# display.net
KiCad netlist of a schematic drawn in Altium Designer
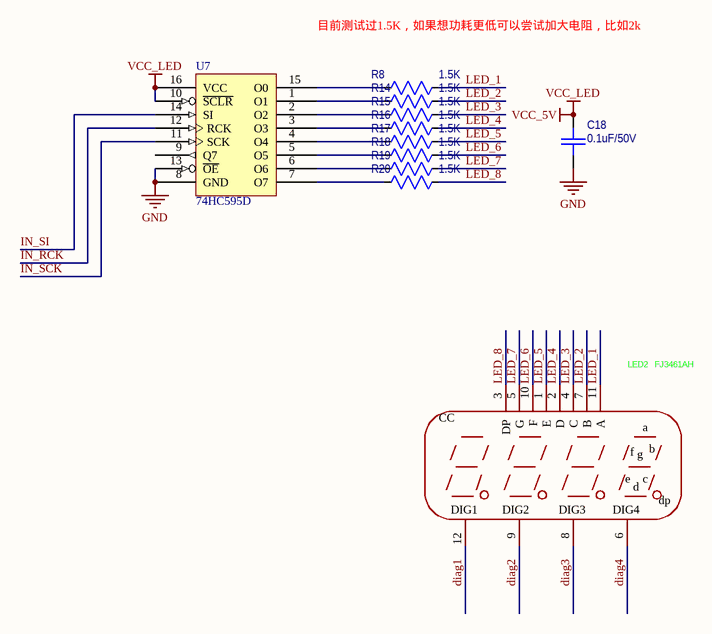
[diagram p0: display.SchDoc]

(export (version "E")
  (design (tool "Eeschema 10.0.6"))
  (components
    (comp (ref "C18")
      (value "0.1uF/50V")
      (footprint "CAPC1608X092N_0603")
      (description "Capacitor, MLCC")
      (fields (field (name "MANUFACTURER") "KEMET") (field (name "PARTNUMBER") "C0603C104M5RACTU"))
      (libsource (lib "Karl") (part "Capacitor_0603"))
    )
    (comp (ref "LED2")
      (value "FJ3461AH")
      (footprint "LED-SEG-TH_12P-L30.0-W14.0-P2.54-S10.26-BL:LED-SEG-TH_12P-L30.0-W14.0-P2.54-S10.26-BL")
      (fields (field (name "MANUFACTURER") "志浩") (field (name "MANUFACTURER PART") "FJ5461AH 红色"))
      (libsource (lib "altium-import") (part "root_0_FJ5461AH 红色_"))
    )
    (comp (ref "R8")
      (value "1.5K")
      (footprint "RESC1608X055N_0603")
      (description "Resistor, Standard")
      (fields (field (name "MANUFACTURER") "Yageo") (field (name "PARTNUMBER") "RC0603FR-1075KL"))
      (libsource (lib "Karl") (part "Resistor_0603"))
    )
    (comp (ref "R14")
      (value "1.5K")
      (footprint "RESC1608X055N_0603")
      (description "Resistor, Standard")
      (fields (field (name "MANUFACTURER") "Yageo") (field (name "PARTNUMBER") "RC0603FR-1075KL"))
      (libsource (lib "Karl") (part "Resistor_0603"))
    )
    (comp (ref "R15")
      (value "1.5K")
      (footprint "RESC1608X055N_0603")
      (description "Resistor, Standard")
      (fields (field (name "MANUFACTURER") "Yageo") (field (name "PARTNUMBER") "RC0603FR-1075KL"))
      (libsource (lib "Karl") (part "Resistor_0603"))
    )
    (comp (ref "R16")
      (value "1.5K")
      (footprint "RESC1608X055N_0603")
      (description "Resistor, Standard")
      (fields (field (name "MANUFACTURER") "Yageo") (field (name "PARTNUMBER") "RC0603FR-1075KL"))
      (libsource (lib "Karl") (part "Resistor_0603"))
    )
    (comp (ref "R17")
      (value "1.5K")
      (footprint "RESC1608X055N_0603")
      (description "Resistor, Standard")
      (fields (field (name "MANUFACTURER") "Yageo") (field (name "PARTNUMBER") "RC0603FR-1075KL"))
      (libsource (lib "Karl") (part "Resistor_0603"))
    )
    (comp (ref "R18")
      (value "1.5K")
      (footprint "RESC1608X055N_0603")
      (description "Resistor, Standard")
      (fields (field (name "MANUFACTURER") "Yageo") (field (name "PARTNUMBER") "RC0603FR-1075KL"))
      (libsource (lib "Karl") (part "Resistor_0603"))
    )
    (comp (ref "R19")
      (value "1.5K")
      (footprint "RESC1608X055N_0603")
      (description "Resistor, Standard")
      (fields (field (name "MANUFACTURER") "Yageo") (field (name "PARTNUMBER") "RC0603FR-1075KL"))
      (libsource (lib "Karl") (part "Resistor_0603"))
    )
    (comp (ref "R20")
      (value "1.5K")
      (footprint "RESC1608X055N_0603")
      (description "Resistor, Standard")
      (fields (field (name "MANUFACTURER") "Yageo") (field (name "PARTNUMBER") "RC0603FR-1075KL"))
      (libsource (lib "Karl") (part "Resistor_0603"))
    )
    (comp (ref "U7")
      (value "74HC595D")
      (footprint "SOIC-16_L9.9-W3.9-P1.27-LS6.0-BL:SOIC-16_L9.9-W3.9-P1.27-LS6.0-BL")
      (libsource (lib "DI16") (part "74HC595"))
    )
  )
  (nets
    (net (code "1") (name "/IN_RCK") (class "Default")
      (node (ref "U7") (pin "12") (pinfunction "RCK_12") (pintype "input"))
    )
    (net (code "2") (name "/IN_SCK") (class "Default")
      (node (ref "U7") (pin "11") (pinfunction "SCK_11") (pintype "input"))
    )
    (net (code "3") (name "/IN_SI") (class "Default")
      (node (ref "U7") (pin "14") (pinfunction "SI_14") (pintype "input"))
    )
    (net (code "4") (name "/LED_1") (class "Default")
      (node (ref "LED2") (pin "11") (pinfunction "A_11") (pintype "passive"))
      (node (ref "R8") (pin "1") (pinfunction "1_1") (pintype "passive"))
    )
    (net (code "5") (name "/LED_2") (class "Default")
      (node (ref "LED2") (pin "7") (pinfunction "B_7") (pintype "passive"))
      (node (ref "R14") (pin "1") (pinfunction "1_1") (pintype "passive"))
    )
    (net (code "6") (name "/LED_3") (class "Default")
      (node (ref "LED2") (pin "4") (pinfunction "C_4") (pintype "passive"))
      (node (ref "R15") (pin "1") (pinfunction "1_1") (pintype "passive"))
    )
    (net (code "7") (name "/LED_4") (class "Default")
      (node (ref "LED2") (pin "2") (pinfunction "D_2") (pintype "passive"))
      (node (ref "R16") (pin "1") (pinfunction "1_1") (pintype "passive"))
    )
    (net (code "8") (name "/LED_5") (class "Default")
      (node (ref "LED2") (pin "1") (pinfunction "E_1") (pintype "passive"))
      (node (ref "R17") (pin "1") (pinfunction "1_1") (pintype "passive"))
    )
    (net (code "9") (name "/LED_6") (class "Default")
      (node (ref "LED2") (pin "10") (pinfunction "F_10") (pintype "passive"))
      (node (ref "R18") (pin "1") (pinfunction "1_1") (pintype "passive"))
    )
    (net (code "10") (name "/LED_7") (class "Default")
      (node (ref "LED2") (pin "5") (pinfunction "G_5") (pintype "passive"))
      (node (ref "R19") (pin "1") (pinfunction "1_1") (pintype "passive"))
    )
    (net (code "11") (name "/LED_8") (class "Default")
      (node (ref "LED2") (pin "3") (pinfunction "DP_3") (pintype "passive"))
      (node (ref "R20") (pin "1") (pinfunction "1_1") (pintype "passive"))
    )
    (net (code "12") (name "/diag1") (class "Default")
      (node (ref "LED2") (pin "12") (pinfunction "DIG1_12") (pintype "passive"))
    )
    (net (code "13") (name "/diag2") (class "Default")
      (node (ref "LED2") (pin "9") (pinfunction "DIG2_9") (pintype "passive"))
    )
    (net (code "14") (name "/diag3") (class "Default")
      (node (ref "LED2") (pin "8") (pinfunction "DIG3_8") (pintype "passive"))
    )
    (net (code "15") (name "/diag4") (class "Default")
      (node (ref "LED2") (pin "6") (pinfunction "DIG4_6") (pintype "passive"))
    )
    (net (code "16") (name "GND") (class "Default")
      (node (ref "C18") (pin "2") (pinfunction "2_2") (pintype "passive"))
      (node (ref "U7") (pin "13") (pinfunction "~{OE}_13") (pintype "input"))
      (node (ref "U7") (pin "8") (pinfunction "GND_8") (pintype "power_in"))
    )
    (net (code "17") (name "Net-(U7-O0)") (class "Default")
      (node (ref "R8") (pin "2") (pinfunction "2_2") (pintype "passive"))
      (node (ref "U7") (pin "15") (pinfunction "O0_15") (pintype "tri_state"))
    )
    (net (code "18") (name "Net-(U7-O1)") (class "Default")
      (node (ref "R14") (pin "2") (pinfunction "2_2") (pintype "passive"))
      (node (ref "U7") (pin "1") (pinfunction "O1_1") (pintype "tri_state"))
    )
    (net (code "19") (name "Net-(U7-O2)") (class "Default")
      (node (ref "R15") (pin "2") (pinfunction "2_2") (pintype "passive"))
      (node (ref "U7") (pin "2") (pinfunction "O2_2") (pintype "tri_state"))
    )
    (net (code "20") (name "Net-(U7-O3)") (class "Default")
      (node (ref "R16") (pin "2") (pinfunction "2_2") (pintype "passive"))
      (node (ref "U7") (pin "3") (pinfunction "O3_3") (pintype "tri_state"))
    )
    (net (code "21") (name "Net-(U7-O4)") (class "Default")
      (node (ref "R17") (pin "2") (pinfunction "2_2") (pintype "passive"))
      (node (ref "U7") (pin "4") (pinfunction "O4_4") (pintype "tri_state"))
    )
    (net (code "22") (name "Net-(U7-O5)") (class "Default")
      (node (ref "R18") (pin "2") (pinfunction "2_2") (pintype "passive"))
      (node (ref "U7") (pin "5") (pinfunction "O5_5") (pintype "tri_state"))
    )
    (net (code "23") (name "Net-(U7-O6)") (class "Default")
      (node (ref "R19") (pin "2") (pinfunction "2_2") (pintype "passive"))
      (node (ref "U7") (pin "6") (pinfunction "O6_6") (pintype "tri_state"))
    )
    (net (code "24") (name "Net-(U7-O7)") (class "Default")
      (node (ref "R20") (pin "2") (pinfunction "2_2") (pintype "passive"))
      (node (ref "U7") (pin "7") (pinfunction "O7_7") (pintype "tri_state"))
    )
    (net (code "25") (name "VCC_5V") (class "Default")
      (node (ref "C18") (pin "1") (pinfunction "1_1") (pintype "passive"))
      (node (ref "U7") (pin "10") (pinfunction "~{SCLR}_10") (pintype "input"))
      (node (ref "U7") (pin "16") (pinfunction "VCC_16") (pintype "power_in"))
    )
    (net (code "26") (name "unconnected-(U7-Q7-Pad9)") (class "Default")
      (node (ref "U7") (pin "9") (pinfunction "Q7_9") (pintype "output"))
    )
  )
)
